# Sheet_1_2026-02-17.net
KiCad netlist of a schematic drawn in Altium Designer
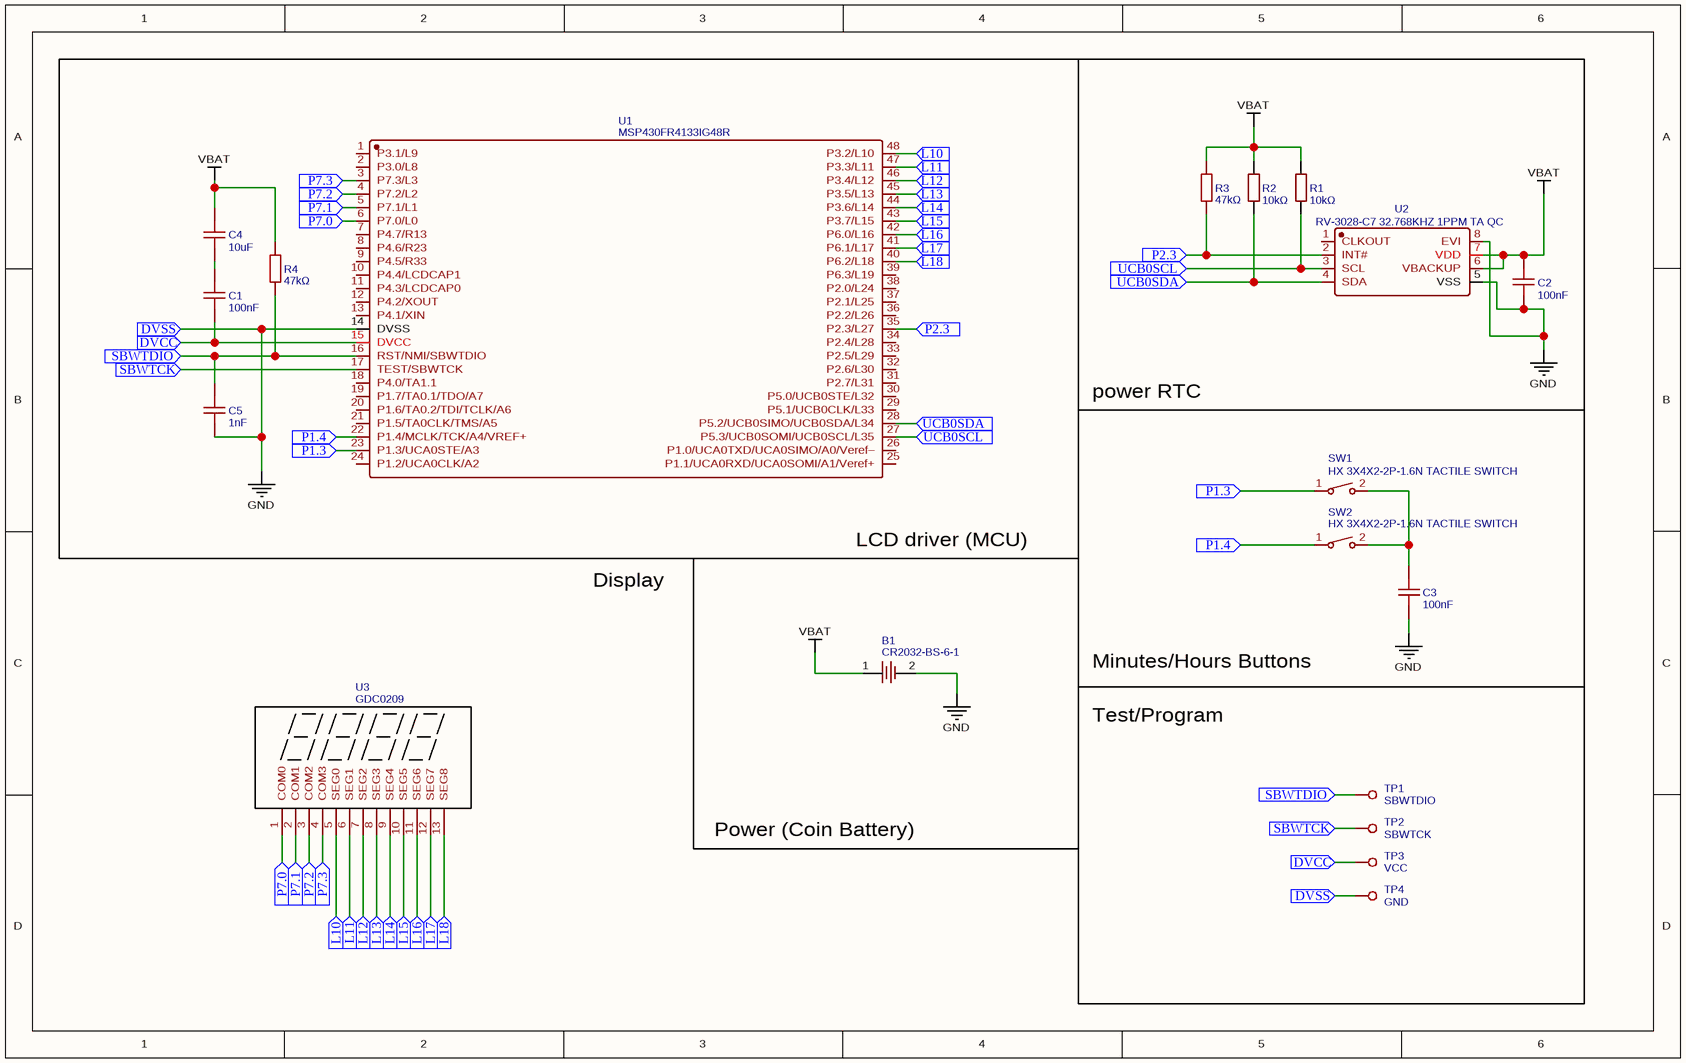
[diagram p0: Sheet_1_2026-02-17.schdoc]

(export (version "E")
  (design (tool "Eeschema 10.0.6"))
  (components
    (comp (ref "B1")
      (value "CR2032-BS-6-1")
      (fields (field (name "MANUFACTURER") "Q&J"))
      (libsource (lib "altium-import") (part "root_0_CR2032-BS-6-1_"))
    )
    (comp (ref "C1")
      (value "100nF")
      (fields
        (field (name "MANUFACTURER") "YAGEO(国巨)")
        (field (name "MANUFACTURER PART") "CC0603KRX7R9BB104")
      )
      (libsource (lib "altium-import") (part "root_3_100nF_"))
    )
    (comp (ref "C2")
      (value "100nF")
      (fields
        (field (name "MANUFACTURER") "YAGEO(国巨)")
        (field (name "MANUFACTURER PART") "CC0603KRX7R9BB104")
      )
      (libsource (lib "altium-import") (part "root_3_100nF_"))
    )
    (comp (ref "C3")
      (value "100nF")
      (fields
        (field (name "MANUFACTURER") "YAGEO(国巨)")
        (field (name "MANUFACTURER PART") "CC0603KRX7R9BB104")
      )
      (libsource (lib "altium-import") (part "root_3_100nF_"))
    )
    (comp (ref "C4")
      (value "10uF")
      (fields
        (field (name "MANUFACTURER") "CCTC(三环)")
        (field (name "MANUFACTURER PART") "TCC0805X5R106M160FTN")
        (field (name "CONTRIBUTOR") "lcsc")
      )
      (libsource (lib "altium-import") (part "root_1_10uF_"))
    )
    (comp (ref "C5")
      (value "1nF")
      (fields
        (field (name "MANUFACTURER") "KYOCERA AVX")
        (field (name "MANUFACTURER PART") "04025C102KAT2A")
        (field (name "VOLTAGE") "50V")
        (field (name "CONTRIBUTOR") "Alexandre De Serres")
      )
      (libsource (lib "altium-import") (part "root_0_1nF_"))
    )
    (comp (ref "R1")
      (value "10kΩ")
      (fields
        (field (name "MANUFACTURER") "UNI-ROYAL(厚声)")
        (field (name "MANUFACTURER PART") "0603WAF1002T5E")
      )
      (libsource (lib "altium-import") (part "root_3_10kΩ_"))
    )
    (comp (ref "R2")
      (value "10kΩ")
      (fields
        (field (name "MANUFACTURER") "UNI-ROYAL(厚声)")
        (field (name "MANUFACTURER PART") "0603WAF1002T5E")
      )
      (libsource (lib "altium-import") (part "root_3_10kΩ_"))
    )
    (comp (ref "R3")
      (value "47kΩ")
      (fields
        (field (name "MANUFACTURER") "Tyohm(幸亚电阻)")
        (field (name "MANUFACTURER PART") "RMC060347K5%N")
        (field (name "CONTRIBUTOR") "LCSC")
      )
      (libsource (lib "altium-import") (part "root_3_47kΩ_"))
    )
    (comp (ref "R4")
      (value "47kΩ")
      (fields
        (field (name "MANUFACTURER") "Tyohm(幸亚电阻)")
        (field (name "MANUFACTURER PART") "RMC060347K5%N")
        (field (name "CONTRIBUTOR") "LCSC")
      )
      (libsource (lib "altium-import") (part "root_3_47kΩ_"))
    )
    (comp (ref "SW1")
      (value "HX 3X4X2-2P-1.6N TACTILE SWITCH")
      (fields
        (field (name "MANUFACTURER") "hanxia(韩下)")
        (field (name "MANUFACTURER PART") "HX 3x4x2-2P-1.6N TACTILE SWITCH")
        (field (name "CONTRIBUTOR") "lcsc")
      )
      (libsource (lib "altium-import") (part "root_0_HX 3X4X2-2P-1.6N TACTILE SWITCH_"))
    )
    (comp (ref "SW2")
      (value "HX 3X4X2-2P-1.6N TACTILE SWITCH")
      (fields
        (field (name "MANUFACTURER") "hanxia(韩下)")
        (field (name "MANUFACTURER PART") "HX 3x4x2-2P-1.6N TACTILE SWITCH")
        (field (name "CONTRIBUTOR") "lcsc")
      )
      (libsource (lib "altium-import") (part "root_0_HX 3X4X2-2P-1.6N TACTILE SWITCH_"))
    )
    (comp (ref "TP1")
      (value "SBWTDIO")
      (fields (field (name "CONTRIBUTOR") "Steve Forest"))
      (libsource (lib "altium-import") (part "root_3_SBWTDIO_"))
    )
    (comp (ref "TP2")
      (value "SBWTCK")
      (fields (field (name "CONTRIBUTOR") "Steve Forest"))
      (libsource (lib "altium-import") (part "root_3_SBWTCK_"))
    )
    (comp (ref "TP3")
      (value "VCC")
      (fields (field (name "CONTRIBUTOR") "Steve Forest"))
      (libsource (lib "altium-import") (part "root_3_VCC_"))
    )
    (comp (ref "TP4")
      (value "GND")
      (fields (field (name "CONTRIBUTOR") "Steve Forest"))
      (libsource (lib "altium-import") (part "root_3_GND_"))
    )
    (comp (ref "U1")
      (value "MSP430FR4133IG48R")
      (fields (field (name "MANUFACTURER") "TI(德州仪器)") (field (name "CONTRIBUTOR") "lcsc"))
      (libsource (lib "altium-import") (part "root_0_MSP430FR4133IG48R_"))
    )
    (comp (ref "U2")
      (value "RV-3028-C7 32.768KHZ 1PPM TA QC")
      (fields
        (field (name "MANUFACTURER") "Micro Crystal(瑞士微晶)")
        (field (name "MANUFACTURER PART") "RV-3028-C7 32.768kHz 1ppm TA QC")
        (field (name "CONTRIBUTOR") "lcsc")
      )
      (libsource (lib "altium-import") (part "root_0_RV-3028-C7 32.768KHZ 1PPM TA QC_"))
    )
    (comp (ref "U3")
      (value "GDC0209")
      (fields
        (field (name "MANUFACTURER") "DALIAN GOOD DISPLAY CO., LTD.")
        (field (name "CONTRIBUTOR") "mskluchko")
      )
      (libsource (lib "altium-import") (part "root_0_GDC0209_"))
    )
  )
  (nets
    (net (code "1") (name "/DVCC") (class "Default")
      (node (ref "C1") (pin "2") (pinfunction "2_2") (pintype "passive"))
      (node (ref "TP3") (pin "1") (pinfunction "1_1") (pintype "passive"))
      (node (ref "U1") (pin "15") (pinfunction "DVCC_15") (pintype "passive"))
    )
    (net (code "2") (name "/L10") (class "Default")
      (node (ref "U1") (pin "48") (pinfunction "P3.2/L10_48") (pintype "passive"))
      (node (ref "U3") (pin "5") (pinfunction "SEG0_5") (pintype "passive"))
    )
    (net (code "3") (name "/L11") (class "Default")
      (node (ref "U1") (pin "47") (pinfunction "P3.3/L11_47") (pintype "passive"))
      (node (ref "U3") (pin "6") (pinfunction "SEG1_6") (pintype "passive"))
    )
    (net (code "4") (name "/L12") (class "Default")
      (node (ref "U1") (pin "46") (pinfunction "P3.4/L12_46") (pintype "passive"))
      (node (ref "U3") (pin "7") (pinfunction "SEG2_7") (pintype "passive"))
    )
    (net (code "5") (name "/L13") (class "Default")
      (node (ref "U1") (pin "45") (pinfunction "P3.5/L13_45") (pintype "passive"))
      (node (ref "U3") (pin "8") (pinfunction "SEG3_8") (pintype "passive"))
    )
    (net (code "6") (name "/L14") (class "Default")
      (node (ref "U1") (pin "44") (pinfunction "P3.6/L14_44") (pintype "passive"))
      (node (ref "U3") (pin "9") (pinfunction "SEG4_9") (pintype "passive"))
    )
    (net (code "7") (name "/L15") (class "Default")
      (node (ref "U1") (pin "43") (pinfunction "P3.7/L15_43") (pintype "passive"))
      (node (ref "U3") (pin "10") (pinfunction "SEG5_10") (pintype "passive"))
    )
    (net (code "8") (name "/L16") (class "Default")
      (node (ref "U1") (pin "42") (pinfunction "P6.0/L16_42") (pintype "passive"))
      (node (ref "U3") (pin "11") (pinfunction "SEG6_11") (pintype "passive"))
    )
    (net (code "9") (name "/L17") (class "Default")
      (node (ref "U1") (pin "41") (pinfunction "P6.1/L17_41") (pintype "passive"))
      (node (ref "U3") (pin "12") (pinfunction "SEG7_12") (pintype "passive"))
    )
    (net (code "10") (name "/L18") (class "Default")
      (node (ref "U1") (pin "40") (pinfunction "P6.2/L18_40") (pintype "passive"))
      (node (ref "U3") (pin "13") (pinfunction "SEG8_13") (pintype "passive"))
    )
    (net (code "11") (name "/P1.3") (class "Default")
      (node (ref "SW1") (pin "1") (pinfunction "1_1") (pintype "passive"))
      (node (ref "U1") (pin "23") (pinfunction "P1.3/UCA0STE/A3_23") (pintype "passive"))
    )
    (net (code "12") (name "/P1.4") (class "Default")
      (node (ref "SW2") (pin "1") (pinfunction "1_1") (pintype "passive"))
      (node (ref "U1") (pin "22") (pinfunction "P1.4/MCLK/TCK/A4/VREF+_22") (pintype "passive"))
    )
    (net (code "13") (name "/P2.3") (class "Default")
      (node (ref "R3") (pin "2") (pinfunction "2_2") (pintype "passive"))
      (node (ref "U1") (pin "35") (pinfunction "P2.3/L27_35") (pintype "passive"))
      (node (ref "U2") (pin "2") (pinfunction "INT#_2") (pintype "passive"))
    )
    (net (code "14") (name "/P7.0") (class "Default")
      (node (ref "U1") (pin "6") (pinfunction "P7.0/L0_6") (pintype "passive"))
      (node (ref "U3") (pin "1") (pinfunction "COM0_1") (pintype "passive"))
    )
    (net (code "15") (name "/P7.1") (class "Default")
      (node (ref "U1") (pin "5") (pinfunction "P7.1/L1_5") (pintype "passive"))
      (node (ref "U3") (pin "2") (pinfunction "COM1_2") (pintype "passive"))
    )
    (net (code "16") (name "/P7.2") (class "Default")
      (node (ref "U1") (pin "4") (pinfunction "P7.2/L2_4") (pintype "passive"))
      (node (ref "U3") (pin "3") (pinfunction "COM2_3") (pintype "passive"))
    )
    (net (code "17") (name "/P7.3") (class "Default")
      (node (ref "U1") (pin "3") (pinfunction "P7.3/L3_3") (pintype "passive"))
      (node (ref "U3") (pin "4") (pinfunction "COM3_4") (pintype "passive"))
    )
    (net (code "18") (name "/SBWTCK") (class "Default")
      (node (ref "TP2") (pin "1") (pinfunction "1_1") (pintype "passive"))
      (node (ref "U1") (pin "17") (pinfunction "TEST/SBWTCK_17") (pintype "passive"))
    )
    (net (code "19") (name "/SBWTDIO") (class "Default")
      (node (ref "C5") (pin "1") (pinfunction "1_1") (pintype "passive"))
      (node (ref "R4") (pin "2") (pinfunction "2_2") (pintype "passive"))
      (node (ref "TP1") (pin "1") (pinfunction "1_1") (pintype "passive"))
      (node (ref "U1") (pin "16") (pinfunction "RST/NMI/SBWTDIO_16") (pintype "passive"))
    )
    (net (code "20") (name "/UCB0SCL") (class "Default")
      (node (ref "R1") (pin "2") (pinfunction "2_2") (pintype "passive"))
      (node (ref "U1") (pin "27") (pinfunction "P5.3/UCB0SOMI/UCB0SCL/L35_27") (pintype "passive"))
      (node (ref "U2") (pin "3") (pinfunction "SCL_3") (pintype "passive"))
    )
    (net (code "21") (name "/UCB0SDA") (class "Default")
      (node (ref "R2") (pin "2") (pinfunction "2_2") (pintype "passive"))
      (node (ref "U1") (pin "28") (pinfunction "P5.2/UCB0SIMO/UCB0SDA/L34_28") (pintype "passive"))
      (node (ref "U2") (pin "4") (pinfunction "SDA_4") (pintype "passive"))
    )
    (net (code "22") (name "GND") (class "Default")
      (node (ref "B1") (pin "2") (pinfunction "2_2") (pintype "passive"))
      (node (ref "C2") (pin "2") (pinfunction "2_2") (pintype "passive"))
      (node (ref "C3") (pin "2") (pinfunction "2_2") (pintype "passive"))
      (node (ref "C5") (pin "2") (pinfunction "2_2") (pintype "passive"))
      (node (ref "TP4") (pin "1") (pinfunction "1_1") (pintype "passive"))
      (node (ref "U1") (pin "14") (pinfunction "DVSS_14") (pintype "passive"))
      (node (ref "U2") (pin "5") (pinfunction "VSS_5") (pintype "passive"))
      (node (ref "U2") (pin "8") (pinfunction "EVI_8") (pintype "passive"))
    )
    (net (code "23") (name "Net-(C1-Pad1)") (class "Default")
      (node (ref "C1") (pin "1") (pinfunction "1_1") (pintype "passive"))
      (node (ref "C4") (pin "1") (pinfunction "1_1") (pintype "passive"))
    )
    (net (code "24") (name "Net-(C3-Pad1)") (class "Default")
      (node (ref "C3") (pin "1") (pinfunction "1_1") (pintype "passive"))
      (node (ref "SW1") (pin "2") (pinfunction "2_2") (pintype "passive"))
      (node (ref "SW2") (pin "2") (pinfunction "2_2") (pintype "passive"))
    )
    (net (code "25") (name "VBAT") (class "Default")
      (node (ref "B1") (pin "1") (pinfunction "1_1") (pintype "passive"))
      (node (ref "C2") (pin "1") (pinfunction "1_1") (pintype "passive"))
      (node (ref "C4") (pin "2") (pinfunction "2_2") (pintype "passive"))
      (node (ref "R1") (pin "1") (pinfunction "1_1") (pintype "passive"))
      (node (ref "R2") (pin "1") (pinfunction "1_1") (pintype "passive"))
      (node (ref "R3") (pin "1") (pinfunction "1_1") (pintype "passive"))
      (node (ref "R4") (pin "1") (pinfunction "1_1") (pintype "passive"))
      (node (ref "U2") (pin "6") (pinfunction "VBACKUP_6") (pintype "passive"))
      (node (ref "U2") (pin "7") (pinfunction "VDD_7") (pintype "passive"))
    )
    (net (code "26") (name "unconnected-(U1-P1.0{slash}UCA0TXD{slash}UCA0SIMO{slash}A0{slash}Veref–-Pad26)") (class "Default")
      (node (ref "U1") (pin "26") (pinfunction "P1.0/UCA0TXD/UCA0SIMO/A0/Veref–_26") (pintype "passive"))
    )
    (net (code "27") (name "unconnected-(U1-P1.1{slash}UCA0RXD{slash}UCA0SOMI{slash}A1{slash}Veref+-Pad25)") (class "Default")
      (node (ref "U1") (pin "25") (pinfunction "P1.1/UCA0RXD/UCA0SOMI/A1/Veref+_25") (pintype "passive"))
    )
    (net (code "28") (name "unconnected-(U1-P1.2{slash}UCA0CLK{slash}A2-Pad24)") (class "Default")
      (node (ref "U1") (pin "24") (pinfunction "P1.2/UCA0CLK/A2_24") (pintype "passive"))
    )
    (net (code "29") (name "unconnected-(U1-P1.5{slash}TA0CLK{slash}TMS{slash}A5-Pad21)") (class "Default")
      (node (ref "U1") (pin "21") (pinfunction "P1.5/TA0CLK/TMS/A5_21") (pintype "passive"))
    )
    (net (code "30") (name "unconnected-(U1-P1.6{slash}TA0.2{slash}TDI{slash}TCLK{slash}A6-Pad20)") (class "Default")
      (node (ref "U1") (pin "20") (pinfunction "P1.6/TA0.2/TDI/TCLK/A6_20") (pintype "passive"))
    )
    (net (code "31") (name "unconnected-(U1-P1.7{slash}TA0.1{slash}TDO{slash}A7-Pad19)") (class "Default")
      (node (ref "U1") (pin "19") (pinfunction "P1.7/TA0.1/TDO/A7_19") (pintype "passive"))
    )
    (net (code "32") (name "unconnected-(U1-P2.0{slash}L24-Pad38)") (class "Default")
      (node (ref "U1") (pin "38") (pinfunction "P2.0/L24_38") (pintype "passive"))
    )
    (net (code "33") (name "unconnected-(U1-P2.1{slash}L25-Pad37)") (class "Default")
      (node (ref "U1") (pin "37") (pinfunction "P2.1/L25_37") (pintype "passive"))
    )
    (net (code "34") (name "unconnected-(U1-P2.2{slash}L26-Pad36)") (class "Default")
      (node (ref "U1") (pin "36") (pinfunction "P2.2/L26_36") (pintype "passive"))
    )
    (net (code "35") (name "unconnected-(U1-P2.4{slash}L28-Pad34)") (class "Default")
      (node (ref "U1") (pin "34") (pinfunction "P2.4/L28_34") (pintype "passive"))
    )
    (net (code "36") (name "unconnected-(U1-P2.5{slash}L29-Pad33)") (class "Default")
      (node (ref "U1") (pin "33") (pinfunction "P2.5/L29_33") (pintype "passive"))
    )
    (net (code "37") (name "unconnected-(U1-P2.6{slash}L30-Pad32)") (class "Default")
      (node (ref "U1") (pin "32") (pinfunction "P2.6/L30_32") (pintype "passive"))
    )
    (net (code "38") (name "unconnected-(U1-P2.7{slash}L31-Pad31)") (class "Default")
      (node (ref "U1") (pin "31") (pinfunction "P2.7/L31_31") (pintype "passive"))
    )
    (net (code "39") (name "unconnected-(U1-P3.0{slash}L8-Pad2)") (class "Default")
      (node (ref "U1") (pin "2") (pinfunction "P3.0/L8_2") (pintype "passive"))
    )
    (net (code "40") (name "unconnected-(U1-P3.1{slash}L9-Pad1)") (class "Default")
      (node (ref "U1") (pin "1") (pinfunction "P3.1/L9_1") (pintype "passive"))
    )
    (net (code "41") (name "unconnected-(U1-P4.0{slash}TA1.1-Pad18)") (class "Default")
      (node (ref "U1") (pin "18") (pinfunction "P4.0/TA1.1_18") (pintype "passive"))
    )
    (net (code "42") (name "unconnected-(U1-P4.1{slash}XIN-Pad13)") (class "Default")
      (node (ref "U1") (pin "13") (pinfunction "P4.1/XIN_13") (pintype "passive"))
    )
    (net (code "43") (name "unconnected-(U1-P4.2{slash}XOUT-Pad12)") (class "Default")
      (node (ref "U1") (pin "12") (pinfunction "P4.2/XOUT_12") (pintype "passive"))
    )
    (net (code "44") (name "unconnected-(U1-P4.3{slash}LCDCAP0-Pad11)") (class "Default")
      (node (ref "U1") (pin "11") (pinfunction "P4.3/LCDCAP0_11") (pintype "passive"))
    )
    (net (code "45") (name "unconnected-(U1-P4.4{slash}LCDCAP1-Pad10)") (class "Default")
      (node (ref "U1") (pin "10") (pinfunction "P4.4/LCDCAP1_10") (pintype "passive"))
    )
    (net (code "46") (name "unconnected-(U1-P4.5{slash}R33-Pad9)") (class "Default")
      (node (ref "U1") (pin "9") (pinfunction "P4.5/R33_9") (pintype "passive"))
    )
    (net (code "47") (name "unconnected-(U1-P4.6{slash}R23-Pad8)") (class "Default")
      (node (ref "U1") (pin "8") (pinfunction "P4.6/R23_8") (pintype "passive"))
    )
    (net (code "48") (name "unconnected-(U1-P4.7{slash}R13-Pad7)") (class "Default")
      (node (ref "U1") (pin "7") (pinfunction "P4.7/R13_7") (pintype "passive"))
    )
    (net (code "49") (name "unconnected-(U1-P5.0{slash}UCB0STE{slash}L32-Pad30)") (class "Default")
      (node (ref "U1") (pin "30") (pinfunction "P5.0/UCB0STE/L32_30") (pintype "passive"))
    )
    (net (code "50") (name "unconnected-(U1-P5.1{slash}UCB0CLK{slash}L33-Pad29)") (class "Default")
      (node (ref "U1") (pin "29") (pinfunction "P5.1/UCB0CLK/L33_29") (pintype "passive"))
    )
    (net (code "51") (name "unconnected-(U1-P6.3{slash}L19-Pad39)") (class "Default")
      (node (ref "U1") (pin "39") (pinfunction "P6.3/L19_39") (pintype "passive"))
    )
    (net (code "52") (name "unconnected-(U2-CLKOUT-Pad1)") (class "Default")
      (node (ref "U2") (pin "1") (pinfunction "CLKOUT_1") (pintype "passive"))
    )
  )
)
